# JacdacMotionDetection_54.net
KiCad netlist of a schematic drawn in Altium Designer
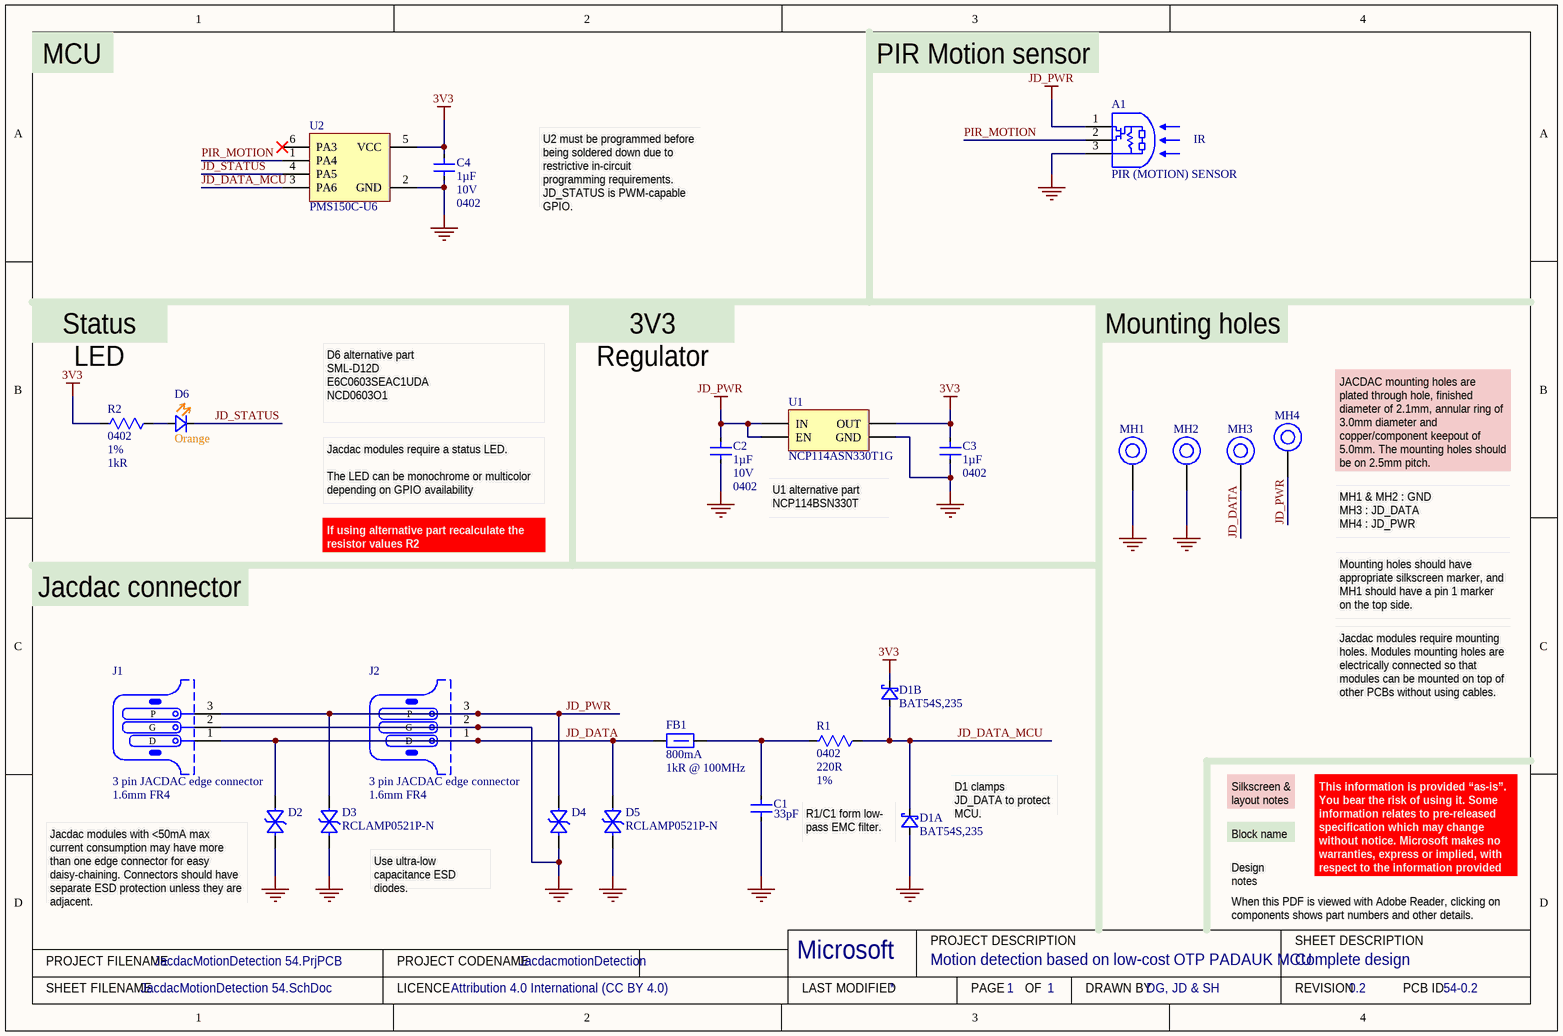
[diagram p0: JacdacMotionDetection 54.SchDoc]

(export (version "E")
  (design (tool "Eeschema 10.0.6"))
  (components
    (comp (ref "A1")
      (value "AM312")
      (footprint "AM312")
      (description "Low Power Ultra-Miniature PIR Sensor")
      (fields (field (name "DESCR") "PIR (MOTION) SENSOR"))
      (libsource (lib "generic") (part "AM312"))
    )
    (comp (ref "C1")
      (value "CL05C330JB5NNNC")
      (footprint "C0402_0.55MM - without outline")
      (description "CAP CER 33PF 50V C0G/NP0 0402")
      (fields
        (field (name "MANUFACTURER") "Samsung")
        (field (name "TOLERANCE") "5%")
        (field (name "CAPACITANCE") "33pF")
      )
      (libsource (lib "Samsung") (part "CL05C330JB5NNNC"))
    )
    (comp (ref "C2")
      (value "CL05A105KP5NNNC")
      (footprint "C0402_0.55MM - without outline")
      (description "CAP CER 1UF 10V X5R 0402")
      (fields
        (field (name "MANUFACTURER") "Samsung")
        (field (name "TOLERANCE") "10%")
        (field (name "CAPACITANCE") "1µF")
        (field (name "VOLTAGE RATING") "10V")
        (field (name "CASE CODE (IMPERIAL)") "0402")
        (field (name "CREATED") "DG")
        (field (name "CHECKED") "?")
      )
      (libsource (lib "Samsung") (part "CL05A105KP5NNNC"))
    )
    (comp (ref "C3")
      (value "CL05A105KP5NNNC")
      (footprint "C0402_0.55MM - without outline")
      (description "CAP CER 1UF 10V X5R 0402")
      (fields
        (field (name "MANUFACTURER") "Samsung")
        (field (name "TOLERANCE") "10%")
        (field (name "CAPACITANCE") "1µF")
        (field (name "CASE CODE (IMPERIAL)") "0402")
        (field (name "CREATED") "DG")
        (field (name "CHECKED") "?")
      )
      (libsource (lib "Samsung") (part "CL05A105KP5NNNC"))
    )
    (comp (ref "C4")
      (value "CL05A105KP5NNNC")
      (footprint "C0402_0.55MM - without outline")
      (description "CAP CER 1UF 10V X5R 0402")
      (fields
        (field (name "MANUFACTURER") "Samsung")
        (field (name "TOLERANCE") "10%")
        (field (name "CAPACITANCE") "1µF")
        (field (name "VOLTAGE RATING") "10V")
        (field (name "CASE CODE (IMPERIAL)") "0402")
        (field (name "CREATED") "DG")
        (field (name "CHECKED") "?")
      )
      (libsource (lib "Samsung") (part "CL05A105KP5NNNC"))
    )
    (comp (ref "D1")
      (value "BAT54S")
      (footprint "NXP-BAT54S-TO-236AB - without outline")
      (description "DIODE ARRAY SCHOTTKY 30V SOT23")
      (fields (field (name "MANUFACTURER") "Nexperia") (field (name "MANUFACTURER PART NUMBER") "BAT54S,235"))
      (libsource (lib "NXP") (part "BAT54S"))
    )
    (comp (ref "D2")
      (value "RCLAMP0521P-N")
      (footprint "TVS 0402 - L")
      (description "Bidirectional 5V (Max) 6V 16V 3.5A (8/20us) 0402 TVS RoHS")
      (fields
        (field (name "MANUFACTURER") "Born Semiconductor")
        (field (name "CREATED BY") "D Gakure")
        (field (name "CHECKED BY") "?")
      )
      (libsource (lib "BornSemiconductor") (part "RCLAMP0521P-N"))
    )
    (comp (ref "D3")
      (value "RCLAMP0521P-N")
      (footprint "TVS 0402 - L")
      (description "Bidirectional 5V (Max) 6V 16V 3.5A (8/20us) 0402 TVS RoHS")
      (fields
        (field (name "MANUFACTURER") "Born Semiconductor")
        (field (name "MANUFACTURER PART NUMBER") "RCLAMP0521P-N")
        (field (name "CREATED BY") "D Gakure")
        (field (name "CHECKED BY") "?")
      )
      (libsource (lib "BornSemiconductor") (part "RCLAMP0521P-N"))
    )
    (comp (ref "D4")
      (value "RCLAMP0521P-N")
      (footprint "TVS 0402 - L")
      (description "Bidirectional 5V (Max) 6V 16V 3.5A (8/20us) 0402 TVS RoHS")
      (fields
        (field (name "MANUFACTURER") "Born Semiconductor")
        (field (name "CREATED BY") "D Gakure")
        (field (name "CHECKED BY") "?")
      )
      (libsource (lib "BornSemiconductor") (part "RCLAMP0521P-N"))
    )
    (comp (ref "D5")
      (value "RCLAMP0521P-N")
      (footprint "TVS 0402 - L")
      (description "Bidirectional 5V (Max) 6V 16V 3.5A (8/20us) 0402 TVS RoHS")
      (fields
        (field (name "MANUFACTURER") "Born Semiconductor")
        (field (name "MANUFACTURER PART NUMBER") "RCLAMP0521P-N")
        (field (name "CREATED BY") "D Gakure")
        (field (name "CHECKED BY") "?")
      )
      (libsource (lib "BornSemiconductor") (part "RCLAMP0521P-N"))
    )
    (comp (ref "D6")
      (value "~")
      (footprint "0603 Orange - without outline")
      (description "LED ORANGE DIFFUSED 1608 SMD")
      (fields
        (field (name "MANUFACTURER") "Everlight Elec")
        (field (name "MANUFACTURER PART NUMBER") "19-217/S2C-AQ1R1B/3T")
        (field (name "COLOUR") "Orange")
      )
      (libsource (lib "EverlightElec") (part "19-217/S2C-AQ1R1B/3T"))
    )
    (comp (ref "FB1")
      (value "TDK MPZ1608S102ATA00")
      (footprint "TDK MPZ1608 0.8mm - without outline")
      (description "0603 1k@100MHz 0.8A chip")
      (fields
        (field (name "TOLERANCE") "25%")
        (field (name "MANUFACTURER") "TDK")
        (field (name "CURRENT RATING") "800mA")
        (field (name "IMPEDANCE") "1kR @ 100MHz")
      )
      (libsource (lib "TDK") (part "TDK MPZ1608S102ATA00"))
    )
    (comp (ref "J1")
      (value "3 pin JACDAC edge connector")
      (footprint "JACDAC_EDGE_CONNECTOR_NO_TRACES")
      (description "3 pin Jacdac edge connector 1.27mm pitch")
      (fields
        (field (name "MANUFACTURER PART NUMBER") "JACDAC_EDGE_CONNECTOR")
        (field (name "PCB TYPE") "1.6mm FR4")
        (field (name "CHECKED BY") "?")
        (field (name "CREATED BY") "D. Gakure")
      )
      (libsource (lib "generic-con") (part "Jacdac edge connector"))
    )
    (comp (ref "J2")
      (value "3 pin JACDAC edge connector")
      (footprint "JACDAC_EDGE_CONNECTOR_NO_TRACES")
      (description "3 pin Jacdac edge connector 1.27mm pitch")
      (fields
        (field (name "MANUFACTURER PART NUMBER") "JACDAC_EDGE_CONNECTOR")
        (field (name "PCB TYPE") "1.6mm FR4")
        (field (name "CHECKED BY") "?")
        (field (name "CREATED BY") "D. Gakure")
      )
      (libsource (lib "generic-con") (part "Jacdac edge connector"))
    )
    (comp (ref "MH1")
      (value "MH_5.0MMK_3.0MMC_2.1MMD_PTH")
      (footprint "MH_5.0MMK_3.0MMC_2.1MMD_PTH")
      (description "Mounting Hole 5.0mm keepout, 3.0mm annualar ring and 2.1mm Drill PTH")
      (libsource (lib "generic") (part "MH_5.0MMK_3.0MMC_2.1MMD_PTH"))
    )
    (comp (ref "MH2")
      (value "MH_5.0MMK_3.0MMC_2.1MMD_PTH")
      (footprint "MH_5.0MMK_3.0MMC_2.1MMD_PTH")
      (description "Mounting Hole 5.0mm keepout, 3.0mm annualar ring and 2.1mm Drill PTH")
      (libsource (lib "generic") (part "MH_5.0MMK_3.0MMC_2.1MMD_PTH"))
    )
    (comp (ref "MH3")
      (value "MH_5.0MMK_3.0MMC_2.1MMD_PTH")
      (footprint "MH_5.0MMK_3.0MMC_2.1MMD_PTH")
      (description "Mounting Hole 5.0mm keepout, 3.0mm annualar ring and 2.1mm Drill PTH")
      (libsource (lib "generic") (part "MH_5.0MMK_3.0MMC_2.1MMD_PTH"))
    )
    (comp (ref "MH4")
      (value "MH_5.0MMK_3.0MMC_2.1MMD_PTH")
      (footprint "MH_5.0MMK_3.0MMC_2.1MMD_PTH")
      (description "Mounting Hole 5.0mm keepout, 3.0mm annualar ring and 2.1mm Drill PTH")
      (libsource (lib "generic") (part "MH_5.0MMK_3.0MMC_2.1MMD_PTH"))
    )
    (comp (ref "R1")
      (value "RC0402FR-07220RL")
      (footprint "R0402 - Without outline")
      (description "RES SMD 220 OHM 1% 1/16W 0402")
      (fields
        (field (name "MANUFACTURER") "Yageo")
        (field (name "CASE CODE (IMPERIAL)") "0402")
        (field (name "RESISTANCE") "220R")
        (field (name "TOLERANCE") "1%")
        (field (name "CREATED") "D.G")
        (field (name "CHECKED") "?")
      )
      (libsource (lib "Yageo") (part "RC0402FR-07220RL"))
    )
    (comp (ref "R2")
      (value "RC0402FR-071KL")
      (footprint "R0402 - Without outline")
      (description "RES SMD 1K OHM 1% 1/16W 0402")
      (fields
        (field (name "MANUFACTURER") "Yageo")
        (field (name "CASE CODE (IMPERIAL)") "0402")
        (field (name "TOLERANCE") "1%")
        (field (name "RESISTANCE") "1kR")
        (field (name "CREATED") "D.G")
        (field (name "CHECKED") "?")
      )
      (libsource (lib "Yageo") (part "RC0402FR-071KL"))
    )
    (comp (ref "U1")
      (value "LDO 3.3V/300 mA")
      (footprint "ON_SEMI-SOT23-5 - without outline")
      (fields
        (field (name "MANUFACTURER") "ON Semiconductor")
        (field (name "MANUFACTURER PART NUMBER") "NCP114ASN330T1G")
        (field (name "CREATED") "DG")
        (field (name "CHECKED") "?")
      )
      (libsource (lib "OnSemiconductor") (part "NCP114ASN330T1G"))
    )
    (comp (ref "U2")
      (value "PMS150C")
      (footprint "SOT23-6")
      (description "8bit OTP Type IO Controller")
      (fields (field (name "MANUFACTURER PART NUMBER") "PMS150C-U6") (field (name "MANUFACTURER") "PADAUK"))
      (libsource (lib "PADAUK") (part "PMS150C"))
    )
  )
  (nets
    (net (code "1") (name "/JD_DATA") (class "Default")
      (node (ref "D2") (pin "1") (pinfunction "K_1") (pintype "passive"))
      (node (ref "D5") (pin "1") (pinfunction "K_1") (pintype "passive"))
      (node (ref "FB1") (pin "1") (pinfunction "1_1") (pintype "passive"))
      (node (ref "J1") (pin "1") (pinfunction "D_1") (pintype "passive"))
      (node (ref "J2") (pin "1") (pinfunction "D_1") (pintype "passive"))
      (node (ref "MH3") (pin "1") (pinfunction "1_1") (pintype "passive"))
    )
    (net (code "2") (name "/JD_DATA_MCU") (class "Default")
      (node (ref "D1") (pin "3") (pinfunction "K_3") (pintype "passive"))
      (node (ref "R1") (pin "1") (pinfunction "1_1") (pintype "passive"))
      (node (ref "U2") (pin "3") (pinfunction "PA6_3") (pintype "passive"))
    )
    (net (code "3") (name "/JD_STATUS") (class "Default")
      (node (ref "D6") (pin "1") (pinfunction "K_1") (pintype "passive"))
      (node (ref "U2") (pin "4") (pinfunction "PA5_4") (pintype "passive"))
    )
    (net (code "4") (name "/PIR_MOTION") (class "Default")
      (node (ref "A1") (pin "2") (pinfunction "OUT_2") (pintype "passive"))
      (node (ref "U2") (pin "1") (pinfunction "PA4_1") (pintype "passive"))
    )
    (net (code "5") (name "3V3") (class "Default")
      (node (ref "C3") (pin "2") (pinfunction "2_2") (pintype "passive"))
      (node (ref "C4") (pin "2") (pinfunction "2_2") (pintype "passive"))
      (node (ref "D1") (pin "2") (pinfunction "K_2") (pintype "passive"))
      (node (ref "R2") (pin "2") (pinfunction "2_2") (pintype "passive"))
      (node (ref "U1") (pin "5") (pinfunction "OUT_5") (pintype "passive"))
      (node (ref "U2") (pin "5") (pinfunction "VCC_5") (pintype "passive"))
    )
    (net (code "6") (name "GND") (class "Default")
      (node (ref "A1") (pin "3") (pinfunction "GND_3") (pintype "passive"))
      (node (ref "C1") (pin "1") (pinfunction "1_1") (pintype "passive"))
      (node (ref "C2") (pin "1") (pinfunction "1_1") (pintype "passive"))
      (node (ref "C3") (pin "1") (pinfunction "1_1") (pintype "passive"))
      (node (ref "C4") (pin "1") (pinfunction "1_1") (pintype "passive"))
      (node (ref "D1") (pin "1") (pinfunction "A_1") (pintype "passive"))
      (node (ref "D2") (pin "2") (pinfunction "A_2") (pintype "passive"))
      (node (ref "D3") (pin "2") (pinfunction "A_2") (pintype "passive"))
      (node (ref "D4") (pin "2") (pinfunction "A_2") (pintype "passive"))
      (node (ref "D5") (pin "2") (pinfunction "A_2") (pintype "passive"))
      (node (ref "J1") (pin "2") (pinfunction "G_2") (pintype "passive"))
      (node (ref "J2") (pin "2") (pinfunction "G_2") (pintype "passive"))
      (node (ref "MH1") (pin "1") (pinfunction "1_1") (pintype "passive"))
      (node (ref "MH2") (pin "1") (pinfunction "1_1") (pintype "passive"))
      (node (ref "U1") (pin "2") (pinfunction "GND_2") (pintype "passive"))
      (node (ref "U2") (pin "2") (pinfunction "GND_2") (pintype "passive"))
    )
    (net (code "7") (name "JD_PWR") (class "Default")
      (node (ref "A1") (pin "1") (pinfunction "VCC_1") (pintype "passive"))
      (node (ref "C2") (pin "2") (pinfunction "2_2") (pintype "passive"))
      (node (ref "D3") (pin "1") (pinfunction "K_1") (pintype "passive"))
      (node (ref "D4") (pin "1") (pinfunction "K_1") (pintype "passive"))
      (node (ref "J1") (pin "3") (pinfunction "P_3") (pintype "passive"))
      (node (ref "J2") (pin "3") (pinfunction "P_3") (pintype "passive"))
      (node (ref "MH4") (pin "1") (pinfunction "1_1") (pintype "passive"))
      (node (ref "U1") (pin "1") (pinfunction "IN_1") (pintype "passive"))
      (node (ref "U1") (pin "3") (pinfunction "EN_3") (pintype "passive"))
    )
    (net (code "8") (name "Net-(C1-Pad2)") (class "Default")
      (node (ref "C1") (pin "2") (pinfunction "2_2") (pintype "passive"))
      (node (ref "FB1") (pin "2") (pinfunction "2_2") (pintype "passive"))
      (node (ref "R1") (pin "2") (pinfunction "2_2") (pintype "passive"))
    )
    (net (code "9") (name "Net-(D6-A)") (class "Default")
      (node (ref "D6") (pin "2") (pinfunction "A_2") (pintype "passive"))
      (node (ref "R2") (pin "1") (pinfunction "1_1") (pintype "passive"))
    )
    (net (code "10") (name "unconnected-(U2-PA3-Pad6)") (class "Default")
      (node (ref "U2") (pin "6") (pinfunction "PA3_6") (pintype "passive+no_connect"))
    )
  )
)
